# Particle-Gateway.net
KiCad netlist of a schematic drawn in EAGLE
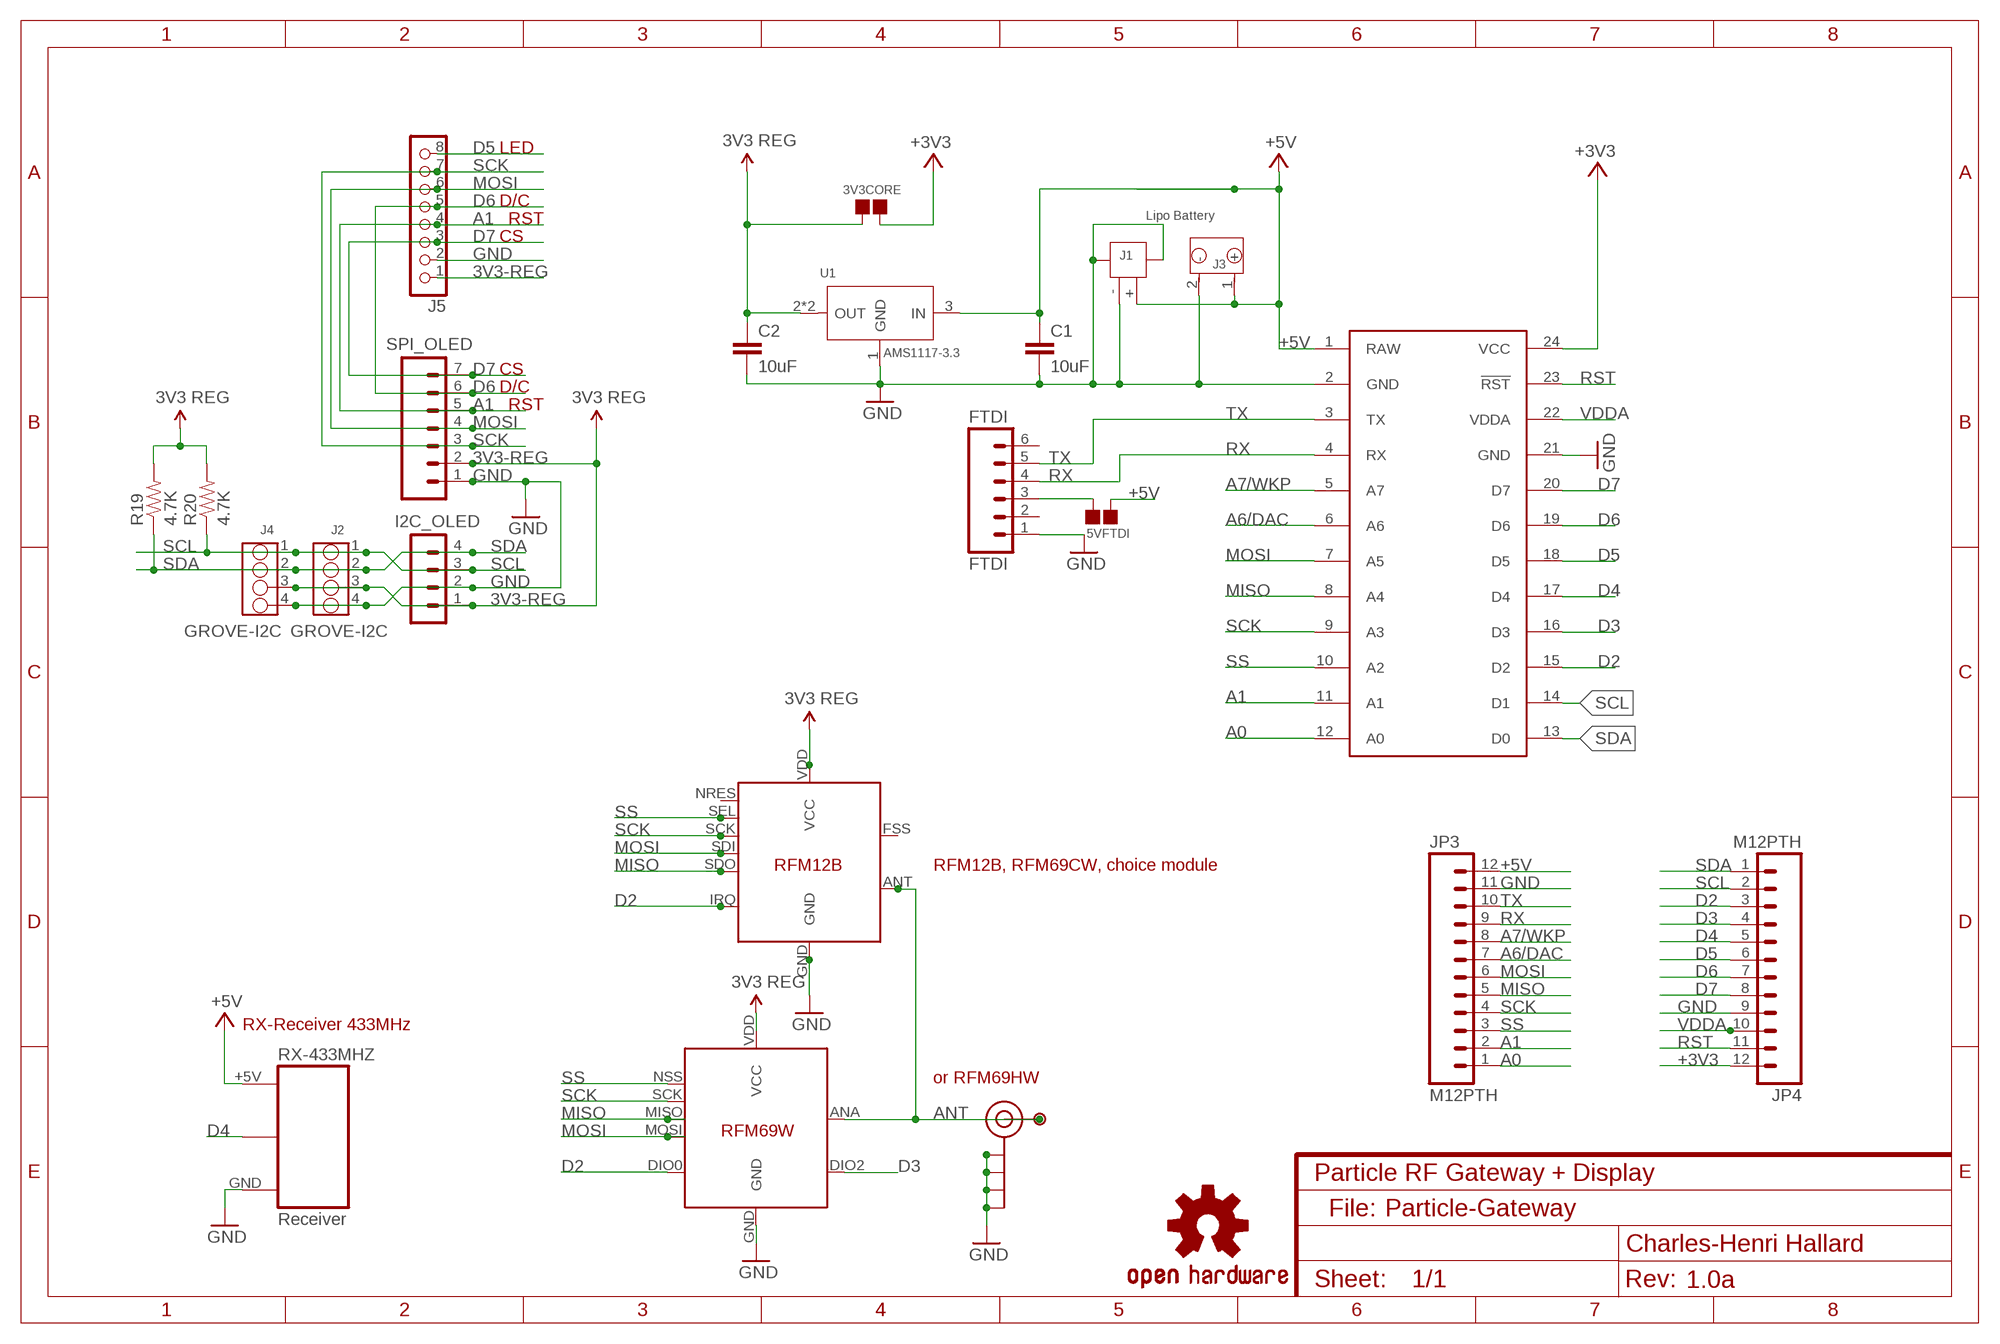
[diagram p0: schematic, sheet 1]

(export (version "E")
  (design (tool "Eeschema 10.0.6"))
  (components
    (comp (ref "3V3CORE")
      (value "PAD-JUMPER-2P")
      (footprint "eagle-import:2P-SMD-1.78X1.27")
      (fields (field (name "PARTNO") "DNP"))
      (libsource (lib "eagle-import") (part "PAD-JUMPER-2P"))
    )
    (comp (ref "5VFTDI")
      (value "PAD-JUMPER-2P")
      (footprint "eagle-import:2P-SMD-1.78X1.27")
      (fields (field (name "PARTNO") "DNP"))
      (libsource (lib "eagle-import") (part "PAD-JUMPER-2P"))
    )
    (comp (ref "C1")
      (value "10uF")
      (footprint "eagle-import:0805-CAP")
      (libsource (lib "eagle-import") (part "CAP0805-CAP"))
    )
    (comp (ref "C2")
      (value "10uF")
      (footprint "eagle-import:0805-CAP")
      (libsource (lib "eagle-import") (part "CAP0805-CAP"))
    )
    (comp (ref "FTDI")
      (value "FTDI")
      (footprint "eagle-import:1X06")
      (libsource (lib "eagle-import") (part "M06SIP"))
    )
    (comp (ref "I2C_OLED")
      (value "CON_HEADER_1X04'SMALL''")
      (footprint "eagle-import:M1X4")
      (libsource (lib "eagle-import") (part "CON_HEADER_1X04'SMALL''"))
    )
    (comp (ref "J$1")
      (value "SMA_EDGE")
      (footprint "eagle-import:SMA-EDGE")
      (libsource (lib "eagle-import") (part "SMA_EDGE"))
    )
    (comp (ref "J1")
      (value "JST-2P-SMD'2.0'")
      (footprint "eagle-import:2P-SMD-2.0-90D")
      (libsource (lib "eagle-import") (part "JST-2P-SMD'2.0'"))
    )
    (comp (ref "J2")
      (value "GROVE-I2C")
      (footprint "eagle-import:4P-2.0-90D")
      (libsource (lib "eagle-import") (part "GROVE-4P-2.0-3470140P1"))
    )
    (comp (ref "J3")
      (value "Lipo Battery")
      (footprint "eagle-import:2P-2.0-90D")
      (libsource (lib "eagle-import") (part "JST-2P-PW-3410070P1"))
    )
    (comp (ref "J4")
      (value "GROVE-I2C")
      (footprint "eagle-import:4P-2.0")
      (libsource (lib "eagle-import") (part "GROVE-4P-2.0-3470130P1"))
    )
    (comp (ref "J5")
      (value "CON_HEADER_1X08-PTH")
      (footprint "eagle-import:M1X8")
      (libsource (lib "eagle-import") (part "CON_HEADER_1X08-PTH"))
    )
    (comp (ref "JP3")
      (value "M12PTH")
      (footprint "eagle-import:1X12-SMALL-PADS")
      (libsource (lib "eagle-import") (part "M12PTH"))
    )
    (comp (ref "JP4")
      (value "M12PTH")
      (footprint "eagle-import:1X12-SMALL-PADS")
      (libsource (lib "eagle-import") (part "M12PTH"))
    )
    (comp (ref "LOGO2")
      (value "OSHW-LOGOL")
      (footprint "eagle-import:OSHW-LOGO-L")
      (libsource (lib "eagle-import") (part "OSHW-LOGOL"))
    )
    (comp (ref "P1")
      (value "PADSMALL")
      (footprint "eagle-import:PAD-SMALL")
      (libsource (lib "eagle-import") (part "PADSMALL"))
    )
    (comp (ref "R19")
      (value "4.7K")
      (footprint "eagle-import:0805-RES")
      (libsource (lib "eagle-import") (part "RESISTOR0805-RES"))
    )
    (comp (ref "R20")
      (value "4.7K")
      (footprint "eagle-import:0805-RES")
      (libsource (lib "eagle-import") (part "RESISTOR0805-RES"))
    )
    (comp (ref "RX-433MHZ")
      (value "Receiver")
      (footprint "eagle-import:RF-LINK_RX_NO_SILK")
      (libsource (lib "eagle-import") (part "RF-LINK_RX"))
    )
    (comp (ref "SPARKCORE")
      (value "SPARK_CORECORE")
      (footprint "eagle-import:SPARK_CORE")
      (libsource (lib "eagle-import") (part "SPARK_CORECORE"))
    )
    (comp (ref "SPI_OLED")
      (value "CON_HEADER_1X07'SMALL'")
      (footprint "eagle-import:M1X7")
      (libsource (lib "eagle-import") (part "CON_HEADER_1X07'SMALL'"))
    )
    (comp (ref "U$2")
      (value "RFM12B")
      (footprint "eagle-import:RFM12B-MINPADS")
      (libsource (lib "eagle-import") (part "RFM12B"))
    )
    (comp (ref "U$3")
      (value "RFM69W")
      (footprint "eagle-import:RFM69W-MINPADS")
      (libsource (lib "eagle-import") (part "RFM69W"))
    )
    (comp (ref "U-FL")
      (value "U.FL")
      (footprint "eagle-import:U.FL")
      (libsource (lib "eagle-import") (part "U.FL"))
    )
    (comp (ref "U1")
      (value "AMS1117-3.3")
      (footprint "eagle-import:SOT223")
      (libsource (lib "eagle-import") (part "CJ1117-3.3-1310190P1"))
    )
  )
  (nets
    (net (code "1") (name "+3V3") (class "Default")
      (node (ref "3V3CORE") (pin "2") (pinfunction "2_2") (pintype "bidirectional"))
      (node (ref "JP4") (pin "12") (pinfunction "12_12") (pintype "passive"))
      (node (ref "SPARKCORE") (pin "24") (pinfunction "VCC_24") (pintype "power_in"))
    )
    (net (code "2") (name "+5V") (class "Default")
      (node (ref "5VFTDI") (pin "1") (pinfunction "1_1") (pintype "bidirectional"))
      (node (ref "C1") (pin "1") (pinfunction "1_1") (pintype "passive"))
      (node (ref "J1") (pin "+") (pinfunction "1_+") (pintype "bidirectional"))
      (node (ref "J3") (pin "1") (pinfunction "+_1") (pintype "bidirectional"))
      (node (ref "JP3") (pin "12") (pinfunction "12_12") (pintype "passive"))
      (node (ref "RX-433MHZ") (pin "+5V") (pinfunction "+5V_+5V") (pintype "power_in"))
      (node (ref "SPARKCORE") (pin "1") (pinfunction "RAW_1") (pintype "power_in"))
      (node (ref "U1") (pin "3") (pinfunction "IN_3") (pintype "bidirectional"))
    )
    (net (code "3") (name "/A0") (class "Default")
      (node (ref "JP3") (pin "1") (pinfunction "1_1") (pintype "passive"))
      (node (ref "SPARKCORE") (pin "12") (pinfunction "A0_12") (pintype "bidirectional"))
    )
    (net (code "4") (name "/A1") (class "Default")
      (node (ref "J5") (pin "4") (pinfunction "4_4") (pintype "passive"))
      (node (ref "JP3") (pin "2") (pinfunction "2_2") (pintype "passive"))
      (node (ref "SPARKCORE") (pin "11") (pinfunction "A1_11") (pintype "bidirectional"))
      (node (ref "SPI_OLED") (pin "5") (pinfunction "5_5") (pintype "passive"))
    )
    (net (code "5") (name "/A6{slash}DAC") (class "Default")
      (node (ref "JP3") (pin "7") (pinfunction "7_7") (pintype "passive"))
      (node (ref "SPARKCORE") (pin "6") (pinfunction "A6_6") (pintype "bidirectional"))
    )
    (net (code "6") (name "/A7{slash}WKP") (class "Default")
      (node (ref "JP3") (pin "8") (pinfunction "8_8") (pintype "passive"))
      (node (ref "SPARKCORE") (pin "5") (pinfunction "A7_5") (pintype "bidirectional"))
    )
    (net (code "7") (name "/ANT") (class "Default")
      (node (ref "J$1") (pin "SIG") (pinfunction "SIGNAL_SIG") (pintype "bidirectional"))
      (node (ref "P1") (pin "1") (pinfunction "1_1") (pintype "bidirectional"))
      (node (ref "U$2") (pin "ANT") (pinfunction "ANT_ANT") (pintype "passive"))
      (node (ref "U$3") (pin "ANA") (pinfunction "ANT_ANA") (pintype "passive"))
      (node (ref "U-FL") (pin "3") (pinfunction "SIGNAL_3") (pintype "passive"))
    )
    (net (code "8") (name "/D2") (class "Default")
      (node (ref "JP4") (pin "3") (pinfunction "3_3") (pintype "passive"))
      (node (ref "SPARKCORE") (pin "15") (pinfunction "D2_15") (pintype "bidirectional"))
      (node (ref "U$2") (pin "IRQ") (pinfunction "IRQ_IRQ") (pintype "open_collector"))
      (node (ref "U$3") (pin "DIO0") (pinfunction "DIO0_DIO0") (pintype "open_collector"))
    )
    (net (code "9") (name "/D3") (class "Default")
      (node (ref "JP4") (pin "4") (pinfunction "4_4") (pintype "passive"))
      (node (ref "SPARKCORE") (pin "16") (pinfunction "D3_16") (pintype "bidirectional"))
      (node (ref "U$3") (pin "DIO2") (pinfunction "DIO2_DIO2") (pintype "open_collector"))
    )
    (net (code "10") (name "/D4") (class "Default")
      (node (ref "JP4") (pin "5") (pinfunction "5_5") (pintype "passive"))
      (node (ref "RX-433MHZ") (pin "DATA@1") (pinfunction "DATA_DATA@1") (pintype "output"))
      (node (ref "RX-433MHZ") (pin "DATA@2") (pinfunction "DATA_DATA@2") (pintype "output"))
      (node (ref "SPARKCORE") (pin "17") (pinfunction "D4_17") (pintype "bidirectional"))
    )
    (net (code "11") (name "/D5") (class "Default")
      (node (ref "J5") (pin "8") (pinfunction "8_8") (pintype "passive"))
      (node (ref "JP4") (pin "6") (pinfunction "6_6") (pintype "passive"))
      (node (ref "SPARKCORE") (pin "18") (pinfunction "D5_18") (pintype "bidirectional"))
    )
    (net (code "12") (name "/D6") (class "Default")
      (node (ref "J5") (pin "5") (pinfunction "5_5") (pintype "passive"))
      (node (ref "JP4") (pin "7") (pinfunction "7_7") (pintype "passive"))
      (node (ref "SPARKCORE") (pin "19") (pinfunction "D6_19") (pintype "bidirectional"))
      (node (ref "SPI_OLED") (pin "6") (pinfunction "6_6") (pintype "passive"))
    )
    (net (code "13") (name "/D7") (class "Default")
      (node (ref "J5") (pin "3") (pinfunction "3_3") (pintype "passive"))
      (node (ref "JP4") (pin "8") (pinfunction "8_8") (pintype "passive"))
      (node (ref "SPARKCORE") (pin "20") (pinfunction "D7_20") (pintype "bidirectional"))
      (node (ref "SPI_OLED") (pin "7") (pinfunction "7_7") (pintype "passive"))
    )
    (net (code "14") (name "/MISO") (class "Default")
      (node (ref "JP3") (pin "5") (pinfunction "5_5") (pintype "passive"))
      (node (ref "SPARKCORE") (pin "8") (pinfunction "A4_8") (pintype "bidirectional"))
      (node (ref "U$2") (pin "SDO") (pinfunction "SDO_SDO") (pintype "output"))
      (node (ref "U$3") (pin "MISO") (pinfunction "MISO_MISO") (pintype "input"))
    )
    (net (code "15") (name "/MOSI") (class "Default")
      (node (ref "J5") (pin "6") (pinfunction "6_6") (pintype "passive"))
      (node (ref "JP3") (pin "6") (pinfunction "6_6") (pintype "passive"))
      (node (ref "SPARKCORE") (pin "7") (pinfunction "A5_7") (pintype "bidirectional"))
      (node (ref "SPI_OLED") (pin "4") (pinfunction "4_4") (pintype "passive"))
      (node (ref "U$2") (pin "SDI") (pinfunction "SDI_SDI") (pintype "input"))
      (node (ref "U$3") (pin "MOSI") (pinfunction "MOSI_MOSI") (pintype "output"))
    )
    (net (code "16") (name "/RST") (class "Default")
      (node (ref "JP4") (pin "11") (pinfunction "11_11") (pintype "passive"))
      (node (ref "SPARKCORE") (pin "23") (pinfunction "~{RST}_23") (pintype "bidirectional"))
    )
    (net (code "17") (name "/RX") (class "Default")
      (node (ref "FTDI") (pin "4") (pinfunction "4_4") (pintype "passive"))
      (node (ref "JP3") (pin "9") (pinfunction "9_9") (pintype "passive"))
      (node (ref "SPARKCORE") (pin "4") (pinfunction "RX_4") (pintype "bidirectional"))
    )
    (net (code "18") (name "/SCK") (class "Default")
      (node (ref "J5") (pin "7") (pinfunction "7_7") (pintype "passive"))
      (node (ref "JP3") (pin "4") (pinfunction "4_4") (pintype "passive"))
      (node (ref "SPARKCORE") (pin "9") (pinfunction "A3_9") (pintype "bidirectional"))
      (node (ref "SPI_OLED") (pin "3") (pinfunction "3_3") (pintype "passive"))
      (node (ref "U$2") (pin "SCK") (pinfunction "SCK_SCK") (pintype "input"))
      (node (ref "U$3") (pin "SCK") (pinfunction "SCK_SCK") (pintype "input"))
    )
    (net (code "19") (name "/SS") (class "Default")
      (node (ref "JP3") (pin "3") (pinfunction "3_3") (pintype "passive"))
      (node (ref "SPARKCORE") (pin "10") (pinfunction "A2_10") (pintype "bidirectional"))
      (node (ref "U$2") (pin "SEL") (pinfunction "SEL_SEL") (pintype "input"))
      (node (ref "U$3") (pin "NSS") (pinfunction "SEL_NSS") (pintype "input"))
    )
    (net (code "20") (name "/TX") (class "Default")
      (node (ref "FTDI") (pin "5") (pinfunction "5_5") (pintype "passive"))
      (node (ref "JP3") (pin "10") (pinfunction "10_10") (pintype "passive"))
      (node (ref "SPARKCORE") (pin "3") (pinfunction "TX_3") (pintype "bidirectional"))
    )
    (net (code "21") (name "/VDDA") (class "Default")
      (node (ref "JP4") (pin "10") (pinfunction "10_10") (pintype "passive"))
      (node (ref "SPARKCORE") (pin "22") (pinfunction "VDDA_22") (pintype "power_in"))
    )
    (net (code "22") (name "3V3 REG") (class "Default")
      (node (ref "3V3CORE") (pin "1") (pinfunction "1_1") (pintype "bidirectional"))
      (node (ref "C2") (pin "1") (pinfunction "1_1") (pintype "passive"))
      (node (ref "I2C_OLED") (pin "1") (pinfunction "1_1") (pintype "passive"))
      (node (ref "J2") (pin "3") (pinfunction "3_3") (pintype "bidirectional"))
      (node (ref "J4") (pin "3") (pinfunction "3_3") (pintype "bidirectional"))
      (node (ref "J5") (pin "1") (pinfunction "1_1") (pintype "passive"))
      (node (ref "R19") (pin "2") (pinfunction "2_2") (pintype "passive"))
      (node (ref "R20") (pin "2") (pinfunction "2_2") (pintype "passive"))
      (node (ref "SPI_OLED") (pin "2") (pinfunction "2_2") (pintype "passive"))
      (node (ref "U$2") (pin "VDD") (pinfunction "VCC_VDD") (pintype "power_in"))
      (node (ref "U$3") (pin "VDD") (pinfunction "VCC_VDD") (pintype "power_in"))
      (node (ref "U1") (pin "2") (pinfunction "OUT_2") (pintype "bidirectional"))
      (node (ref "U1") (pin "TER") (pinfunction "OUT_TER") (pintype "bidirectional"))
    )
    (net (code "23") (name "GND") (class "Default")
      (node (ref "C1") (pin "2") (pinfunction "2_2") (pintype "passive"))
      (node (ref "C2") (pin "2") (pinfunction "2_2") (pintype "passive"))
      (node (ref "FTDI") (pin "1") (pinfunction "1_1") (pintype "passive"))
      (node (ref "I2C_OLED") (pin "2") (pinfunction "2_2") (pintype "passive"))
      (node (ref "J$1") (pin "GND@0") (pinfunction "GND_GND@0") (pintype "bidirectional"))
      (node (ref "J$1") (pin "GND@1") (pinfunction "GND_GND@1") (pintype "bidirectional"))
      (node (ref "J$1") (pin "GND@2") (pinfunction "GND_GND@2") (pintype "bidirectional"))
      (node (ref "J$1") (pin "GND@3") (pinfunction "GND_GND@3") (pintype "bidirectional"))
      (node (ref "J1") (pin "-") (pinfunction "2_-") (pintype "bidirectional"))
      (node (ref "J1") (pin "3") (pinfunction "3_3") (pintype "bidirectional"))
      (node (ref "J1") (pin "4") (pinfunction "4_4") (pintype "bidirectional"))
      (node (ref "J2") (pin "4") (pinfunction "4_4") (pintype "bidirectional"))
      (node (ref "J3") (pin "2") (pinfunction "-_2") (pintype "bidirectional"))
      (node (ref "J4") (pin "4") (pinfunction "4_4") (pintype "bidirectional"))
      (node (ref "J5") (pin "2") (pinfunction "2_2") (pintype "passive"))
      (node (ref "JP3") (pin "11") (pinfunction "11_11") (pintype "passive"))
      (node (ref "JP4") (pin "9") (pinfunction "9_9") (pintype "passive"))
      (node (ref "RX-433MHZ") (pin "GND") (pinfunction "GND_GND") (pintype "power_in"))
      (node (ref "SPARKCORE") (pin "2") (pinfunction "GND_2") (pintype "power_in"))
      (node (ref "SPARKCORE") (pin "21") (pinfunction "GND_21") (pintype "power_in"))
      (node (ref "SPI_OLED") (pin "1") (pinfunction "1_1") (pintype "passive"))
      (node (ref "U$2") (pin "GND") (pinfunction "GND_GND") (pintype "power_in"))
      (node (ref "U$3") (pin "GND") (pinfunction "GND_GND") (pintype "power_in"))
      (node (ref "U-FL") (pin "1") (pinfunction "GND_1") (pintype "passive"))
      (node (ref "U-FL") (pin "2") (pinfunction "GND_2") (pintype "passive"))
      (node (ref "U1") (pin "1") (pinfunction "GND_1") (pintype "bidirectional"))
    )
    (net (code "24") (name "Net-(5VFTDI-Pad2)") (class "Default")
      (node (ref "5VFTDI") (pin "2") (pinfunction "2_2") (pintype "bidirectional"))
      (node (ref "FTDI") (pin "3") (pinfunction "3_3") (pintype "passive"))
    )
    (net (code "25") (name "SCL") (class "Default")
      (node (ref "I2C_OLED") (pin "3") (pinfunction "3_3") (pintype "passive"))
      (node (ref "J2") (pin "1") (pinfunction "1_1") (pintype "bidirectional"))
      (node (ref "J4") (pin "1") (pinfunction "1_1") (pintype "bidirectional"))
      (node (ref "JP4") (pin "2") (pinfunction "2_2") (pintype "passive"))
      (node (ref "R20") (pin "1") (pinfunction "1_1") (pintype "passive"))
      (node (ref "SPARKCORE") (pin "14") (pinfunction "D1_14") (pintype "bidirectional"))
    )
    (net (code "26") (name "SDA") (class "Default")
      (node (ref "I2C_OLED") (pin "4") (pinfunction "4_4") (pintype "passive"))
      (node (ref "J2") (pin "2") (pinfunction "2_2") (pintype "bidirectional"))
      (node (ref "J4") (pin "2") (pinfunction "2_2") (pintype "bidirectional"))
      (node (ref "JP4") (pin "1") (pinfunction "1_1") (pintype "passive"))
      (node (ref "R19") (pin "1") (pinfunction "1_1") (pintype "passive"))
      (node (ref "SPARKCORE") (pin "13") (pinfunction "D0_13") (pintype "bidirectional"))
    )
    (net (code "27") (name "unconnected-(FTDI-Pad2)") (class "Default")
      (node (ref "FTDI") (pin "2") (pinfunction "2_2") (pintype "passive"))
    )
    (net (code "28") (name "unconnected-(FTDI-Pad6)") (class "Default")
      (node (ref "FTDI") (pin "6") (pinfunction "6_6") (pintype "passive"))
    )
    (net (code "29") (name "unconnected-(U$2-FFS-PadFSS)") (class "Default")
      (node (ref "U$2") (pin "FSS") (pinfunction "FFS_FSS") (pintype "bidirectional"))
    )
    (net (code "30") (name "unconnected-(U$2-PadNRES)") (class "Default")
      (node (ref "U$2") (pin "NRES") (pinfunction "NRES_NRES") (pintype "input"))
    )
  )
)
